# merch-hat.net
KiCad netlist of a schematic drawn in EAGLE
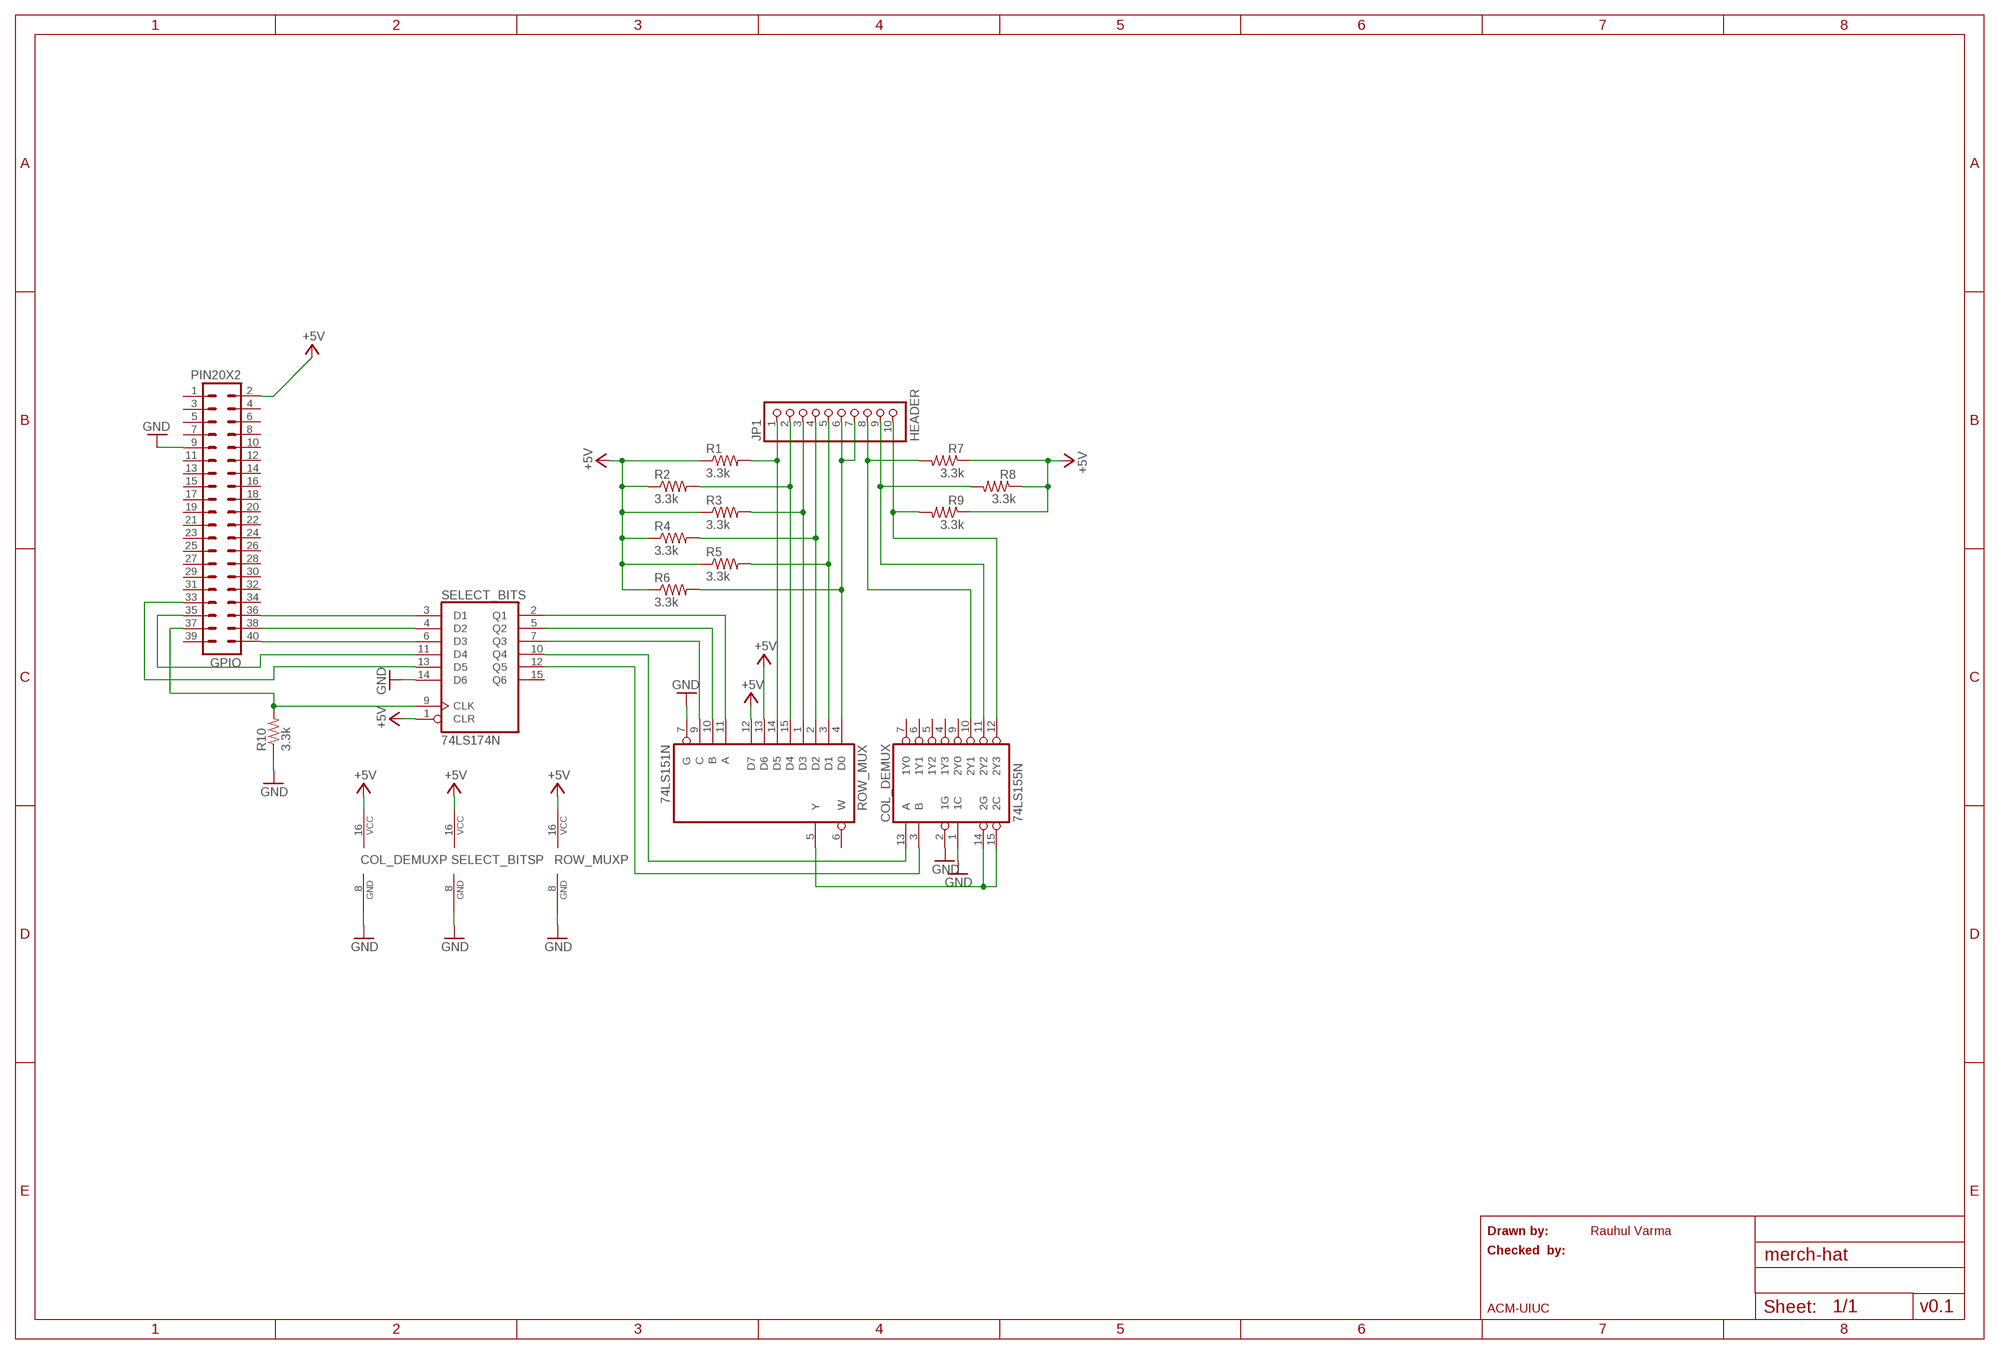
[diagram p0: schematic, sheet 1]

(export (version "E")
  (design (tool "Eeschema 10.0.6"))
  (components
    (comp (ref "COL_DEMUX")
      (value "74LS155N")
      (footprint "eagle-import:DIL16")
      (libsource (lib "eagle-import") (part "74155NLS"))
    )
    (comp (ref "GPIO")
      (value "PIN20X2")
      (footprint "eagle-import:PIN_20X2")
      (libsource (lib "eagle-import") (part "PIN20X2"))
    )
    (comp (ref "JP1")
      (value "HEADER")
      (footprint "eagle-import:1X10")
      (libsource (lib "eagle-import") (part "PINHD-1X10"))
    )
    (comp (ref "R1")
      (value "3.3k")
      (footprint "eagle-import:0207_10")
      (libsource (lib "eagle-import") (part "R-US_0207/10"))
    )
    (comp (ref "R2")
      (value "3.3k")
      (footprint "eagle-import:0207_10")
      (libsource (lib "eagle-import") (part "R-US_0207/10"))
    )
    (comp (ref "R3")
      (value "3.3k")
      (footprint "eagle-import:0207_10")
      (libsource (lib "eagle-import") (part "R-US_0207/10"))
    )
    (comp (ref "R4")
      (value "3.3k")
      (footprint "eagle-import:0207_10")
      (libsource (lib "eagle-import") (part "R-US_0207/10"))
    )
    (comp (ref "R5")
      (value "3.3k")
      (footprint "eagle-import:0207_10")
      (libsource (lib "eagle-import") (part "R-US_0207/10"))
    )
    (comp (ref "R6")
      (value "3.3k")
      (footprint "eagle-import:0207_10")
      (libsource (lib "eagle-import") (part "R-US_0207/10"))
    )
    (comp (ref "R7")
      (value "3.3k")
      (footprint "eagle-import:0207_10")
      (libsource (lib "eagle-import") (part "R-US_0207/10"))
    )
    (comp (ref "R8")
      (value "3.3k")
      (footprint "eagle-import:0207_10")
      (libsource (lib "eagle-import") (part "R-US_0207/10"))
    )
    (comp (ref "R9")
      (value "3.3k")
      (footprint "eagle-import:0207_10")
      (libsource (lib "eagle-import") (part "R-US_0207/10"))
    )
    (comp (ref "R10")
      (value "3.3k")
      (footprint "eagle-import:0207_10")
      (libsource (lib "eagle-import") (part "R-US_0207/10"))
    )
    (comp (ref "ROW_MUX")
      (value "74LS151N")
      (footprint "eagle-import:DIL16")
      (libsource (lib "eagle-import") (part "74151NLS"))
    )
    (comp (ref "SELECT_BITS")
      (value "74LS174N")
      (footprint "eagle-import:DIL16")
      (libsource (lib "eagle-import") (part "74174NLS"))
    )
  )
  (nets
    (net (code "1") (name "+5V") (class "Default")
      (node (ref "COL_DEMUX") (pin "16") (pinfunction "VCC_16") (pintype "power_in"))
      (node (ref "GPIO") (pin "2") (pinfunction "2_2") (pintype "passive"))
      (node (ref "R1") (pin "1") (pinfunction "1_1") (pintype "passive"))
      (node (ref "R2") (pin "1") (pinfunction "1_1") (pintype "passive"))
      (node (ref "R3") (pin "1") (pinfunction "1_1") (pintype "passive"))
      (node (ref "R4") (pin "1") (pinfunction "1_1") (pintype "passive"))
      (node (ref "R5") (pin "1") (pinfunction "1_1") (pintype "passive"))
      (node (ref "R6") (pin "1") (pinfunction "1_1") (pintype "passive"))
      (node (ref "R7") (pin "1") (pinfunction "1_1") (pintype "passive"))
      (node (ref "R8") (pin "1") (pinfunction "1_1") (pintype "passive"))
      (node (ref "R9") (pin "1") (pinfunction "1_1") (pintype "passive"))
      (node (ref "ROW_MUX") (pin "12") (pinfunction "D7_12") (pintype "input"))
      (node (ref "ROW_MUX") (pin "13") (pinfunction "D6_13") (pintype "input"))
      (node (ref "ROW_MUX") (pin "16") (pinfunction "VCC_16") (pintype "power_in"))
      (node (ref "SELECT_BITS") (pin "1") (pinfunction "CLR_1") (pintype "input"))
      (node (ref "SELECT_BITS") (pin "16") (pinfunction "VCC_16") (pintype "power_in"))
    )
    (net (code "2") (name "GND") (class "Default")
      (node (ref "COL_DEMUX") (pin "1") (pinfunction "1C_1") (pintype "input"))
      (node (ref "COL_DEMUX") (pin "2") (pinfunction "1G_2") (pintype "input"))
      (node (ref "COL_DEMUX") (pin "8") (pinfunction "GND_8") (pintype "power_in"))
      (node (ref "GPIO") (pin "9") (pinfunction "9_9") (pintype "passive"))
      (node (ref "R10") (pin "1") (pinfunction "1_1") (pintype "passive"))
      (node (ref "ROW_MUX") (pin "7") (pinfunction "G_7") (pintype "input"))
      (node (ref "ROW_MUX") (pin "8") (pinfunction "GND_8") (pintype "power_in"))
      (node (ref "SELECT_BITS") (pin "14") (pinfunction "D6_14") (pintype "input"))
      (node (ref "SELECT_BITS") (pin "8") (pinfunction "GND_8") (pintype "power_in"))
    )
    (net (code "3") (name "Net-(COL_DEMUXA-2C)") (class "Default")
      (node (ref "COL_DEMUX") (pin "14") (pinfunction "2G_14") (pintype "input"))
      (node (ref "COL_DEMUX") (pin "15") (pinfunction "2C_15") (pintype "input"))
      (node (ref "ROW_MUX") (pin "5") (pinfunction "Y_5") (pintype "output"))
    )
    (net (code "4") (name "Net-(COL_DEMUXA-2Y1)") (class "Default")
      (node (ref "COL_DEMUX") (pin "10") (pinfunction "2Y1_10") (pintype "output"))
      (node (ref "JP1") (pin "8") (pinfunction "8_8") (pintype "passive"))
      (node (ref "R7") (pin "2") (pinfunction "2_2") (pintype "passive"))
    )
    (net (code "5") (name "Net-(COL_DEMUXA-2Y2)") (class "Default")
      (node (ref "COL_DEMUX") (pin "11") (pinfunction "2Y2_11") (pintype "output"))
      (node (ref "JP1") (pin "9") (pinfunction "9_9") (pintype "passive"))
      (node (ref "R8") (pin "2") (pinfunction "2_2") (pintype "passive"))
    )
    (net (code "6") (name "Net-(COL_DEMUXA-2Y3)") (class "Default")
      (node (ref "COL_DEMUX") (pin "12") (pinfunction "2Y3_12") (pintype "output"))
      (node (ref "JP1") (pin "10") (pinfunction "10_10") (pintype "passive"))
      (node (ref "R9") (pin "2") (pinfunction "2_2") (pintype "passive"))
    )
    (net (code "7") (name "Net-(COL_DEMUXA-A)") (class "Default")
      (node (ref "COL_DEMUX") (pin "13") (pinfunction "A_13") (pintype "input"))
      (node (ref "SELECT_BITS") (pin "10") (pinfunction "Q4_10") (pintype "output"))
    )
    (net (code "8") (name "Net-(COL_DEMUXA-B)") (class "Default")
      (node (ref "COL_DEMUX") (pin "3") (pinfunction "B_3") (pintype "input"))
      (node (ref "SELECT_BITS") (pin "12") (pinfunction "Q5_12") (pintype "output"))
    )
    (net (code "9") (name "Net-(ROW_MUXA-A)") (class "Default")
      (node (ref "ROW_MUX") (pin "11") (pinfunction "A_11") (pintype "input"))
      (node (ref "SELECT_BITS") (pin "2") (pinfunction "Q1_2") (pintype "output"))
    )
    (net (code "10") (name "Net-(ROW_MUXA-B)") (class "Default")
      (node (ref "ROW_MUX") (pin "10") (pinfunction "B_10") (pintype "input"))
      (node (ref "SELECT_BITS") (pin "5") (pinfunction "Q2_5") (pintype "output"))
    )
    (net (code "11") (name "Net-(ROW_MUXA-C)") (class "Default")
      (node (ref "ROW_MUX") (pin "9") (pinfunction "C_9") (pintype "input"))
      (node (ref "SELECT_BITS") (pin "7") (pinfunction "Q3_7") (pintype "output"))
    )
    (net (code "12") (name "Net-(ROW_MUXA-D0)") (class "Default")
      (node (ref "JP1") (pin "6") (pinfunction "6_6") (pintype "passive"))
      (node (ref "JP1") (pin "7") (pinfunction "7_7") (pintype "passive"))
      (node (ref "R6") (pin "2") (pinfunction "2_2") (pintype "passive"))
      (node (ref "ROW_MUX") (pin "4") (pinfunction "D0_4") (pintype "input"))
    )
    (net (code "13") (name "Net-(ROW_MUXA-D1)") (class "Default")
      (node (ref "JP1") (pin "5") (pinfunction "5_5") (pintype "passive"))
      (node (ref "R5") (pin "2") (pinfunction "2_2") (pintype "passive"))
      (node (ref "ROW_MUX") (pin "3") (pinfunction "D1_3") (pintype "input"))
    )
    (net (code "14") (name "Net-(ROW_MUXA-D2)") (class "Default")
      (node (ref "JP1") (pin "4") (pinfunction "4_4") (pintype "passive"))
      (node (ref "R4") (pin "2") (pinfunction "2_2") (pintype "passive"))
      (node (ref "ROW_MUX") (pin "2") (pinfunction "D2_2") (pintype "input"))
    )
    (net (code "15") (name "Net-(ROW_MUXA-D3)") (class "Default")
      (node (ref "JP1") (pin "3") (pinfunction "3_3") (pintype "passive"))
      (node (ref "R3") (pin "2") (pinfunction "2_2") (pintype "passive"))
      (node (ref "ROW_MUX") (pin "1") (pinfunction "D3_1") (pintype "input"))
    )
    (net (code "16") (name "Net-(ROW_MUXA-D4)") (class "Default")
      (node (ref "JP1") (pin "2") (pinfunction "2_2") (pintype "passive"))
      (node (ref "R2") (pin "2") (pinfunction "2_2") (pintype "passive"))
      (node (ref "ROW_MUX") (pin "15") (pinfunction "D4_15") (pintype "input"))
    )
    (net (code "17") (name "Net-(ROW_MUXA-D5)") (class "Default")
      (node (ref "JP1") (pin "1") (pinfunction "1_1") (pintype "passive"))
      (node (ref "R1") (pin "2") (pinfunction "2_2") (pintype "passive"))
      (node (ref "ROW_MUX") (pin "14") (pinfunction "D5_14") (pintype "input"))
    )
    (net (code "18") (name "Net-(SELECT_BITSA-CLK)") (class "Default")
      (node (ref "GPIO") (pin "37") (pinfunction "37_37") (pintype "passive"))
      (node (ref "R10") (pin "2") (pinfunction "2_2") (pintype "passive"))
      (node (ref "SELECT_BITS") (pin "9") (pinfunction "CLK_9") (pintype "input"))
    )
    (net (code "19") (name "Net-(SELECT_BITSA-D1)") (class "Default")
      (node (ref "GPIO") (pin "36") (pinfunction "36_36") (pintype "passive"))
      (node (ref "SELECT_BITS") (pin "3") (pinfunction "D1_3") (pintype "input"))
    )
    (net (code "20") (name "Net-(SELECT_BITSA-D2)") (class "Default")
      (node (ref "GPIO") (pin "38") (pinfunction "38_38") (pintype "passive"))
      (node (ref "SELECT_BITS") (pin "4") (pinfunction "D2_4") (pintype "input"))
    )
    (net (code "21") (name "Net-(SELECT_BITSA-D3)") (class "Default")
      (node (ref "GPIO") (pin "40") (pinfunction "40_40") (pintype "passive"))
      (node (ref "SELECT_BITS") (pin "6") (pinfunction "D3_6") (pintype "input"))
    )
    (net (code "22") (name "Net-(SELECT_BITSA-D4)") (class "Default")
      (node (ref "GPIO") (pin "35") (pinfunction "35_35") (pintype "passive"))
      (node (ref "SELECT_BITS") (pin "11") (pinfunction "D4_11") (pintype "input"))
    )
    (net (code "23") (name "Net-(SELECT_BITSA-D5)") (class "Default")
      (node (ref "GPIO") (pin "33") (pinfunction "33_33") (pintype "passive"))
      (node (ref "SELECT_BITS") (pin "13") (pinfunction "D5_13") (pintype "input"))
    )
    (net (code "24") (name "unconnected-(COL_DEMUXA-1Y0-Pad7)") (class "Default")
      (node (ref "COL_DEMUX") (pin "7") (pinfunction "1Y0_7") (pintype "output"))
    )
    (net (code "25") (name "unconnected-(COL_DEMUXA-1Y1-Pad6)") (class "Default")
      (node (ref "COL_DEMUX") (pin "6") (pinfunction "1Y1_6") (pintype "output"))
    )
    (net (code "26") (name "unconnected-(COL_DEMUXA-1Y2-Pad5)") (class "Default")
      (node (ref "COL_DEMUX") (pin "5") (pinfunction "1Y2_5") (pintype "output"))
    )
    (net (code "27") (name "unconnected-(COL_DEMUXA-1Y3-Pad4)") (class "Default")
      (node (ref "COL_DEMUX") (pin "4") (pinfunction "1Y3_4") (pintype "output"))
    )
    (net (code "28") (name "unconnected-(COL_DEMUXA-2Y0-Pad9)") (class "Default")
      (node (ref "COL_DEMUX") (pin "9") (pinfunction "2Y0_9") (pintype "output"))
    )
    (net (code "29") (name "unconnected-(GPIO-Pad1)") (class "Default")
      (node (ref "GPIO") (pin "1") (pinfunction "1_1") (pintype "passive"))
    )
    (net (code "30") (name "unconnected-(GPIO-Pad3)") (class "Default")
      (node (ref "GPIO") (pin "3") (pinfunction "3_3") (pintype "passive"))
    )
    (net (code "31") (name "unconnected-(GPIO-Pad4)") (class "Default")
      (node (ref "GPIO") (pin "4") (pinfunction "4_4") (pintype "passive"))
    )
    (net (code "32") (name "unconnected-(GPIO-Pad5)") (class "Default")
      (node (ref "GPIO") (pin "5") (pinfunction "5_5") (pintype "passive"))
    )
    (net (code "33") (name "unconnected-(GPIO-Pad6)") (class "Default")
      (node (ref "GPIO") (pin "6") (pinfunction "6_6") (pintype "passive"))
    )
    (net (code "34") (name "unconnected-(GPIO-Pad7)") (class "Default")
      (node (ref "GPIO") (pin "7") (pinfunction "7_7") (pintype "passive"))
    )
    (net (code "35") (name "unconnected-(GPIO-Pad8)") (class "Default")
      (node (ref "GPIO") (pin "8") (pinfunction "8_8") (pintype "passive"))
    )
    (net (code "36") (name "unconnected-(GPIO-Pad10)") (class "Default")
      (node (ref "GPIO") (pin "10") (pinfunction "10_10") (pintype "passive"))
    )
    (net (code "37") (name "unconnected-(GPIO-Pad11)") (class "Default")
      (node (ref "GPIO") (pin "11") (pinfunction "11_11") (pintype "passive"))
    )
    (net (code "38") (name "unconnected-(GPIO-Pad12)") (class "Default")
      (node (ref "GPIO") (pin "12") (pinfunction "12_12") (pintype "passive"))
    )
    (net (code "39") (name "unconnected-(GPIO-Pad13)") (class "Default")
      (node (ref "GPIO") (pin "13") (pinfunction "13_13") (pintype "passive"))
    )
    (net (code "40") (name "unconnected-(GPIO-Pad14)") (class "Default")
      (node (ref "GPIO") (pin "14") (pinfunction "14_14") (pintype "passive"))
    )
    (net (code "41") (name "unconnected-(GPIO-Pad15)") (class "Default")
      (node (ref "GPIO") (pin "15") (pinfunction "15_15") (pintype "passive"))
    )
    (net (code "42") (name "unconnected-(GPIO-Pad16)") (class "Default")
      (node (ref "GPIO") (pin "16") (pinfunction "16_16") (pintype "passive"))
    )
    (net (code "43") (name "unconnected-(GPIO-Pad17)") (class "Default")
      (node (ref "GPIO") (pin "17") (pinfunction "17_17") (pintype "passive"))
    )
    (net (code "44") (name "unconnected-(GPIO-Pad18)") (class "Default")
      (node (ref "GPIO") (pin "18") (pinfunction "18_18") (pintype "passive"))
    )
    (net (code "45") (name "unconnected-(GPIO-Pad19)") (class "Default")
      (node (ref "GPIO") (pin "19") (pinfunction "19_19") (pintype "passive"))
    )
    (net (code "46") (name "unconnected-(GPIO-Pad20)") (class "Default")
      (node (ref "GPIO") (pin "20") (pinfunction "20_20") (pintype "passive"))
    )
    (net (code "47") (name "unconnected-(GPIO-Pad21)") (class "Default")
      (node (ref "GPIO") (pin "21") (pinfunction "21_21") (pintype "passive"))
    )
    (net (code "48") (name "unconnected-(GPIO-Pad22)") (class "Default")
      (node (ref "GPIO") (pin "22") (pinfunction "22_22") (pintype "passive"))
    )
    (net (code "49") (name "unconnected-(GPIO-Pad23)") (class "Default")
      (node (ref "GPIO") (pin "23") (pinfunction "23_23") (pintype "passive"))
    )
    (net (code "50") (name "unconnected-(GPIO-Pad24)") (class "Default")
      (node (ref "GPIO") (pin "24") (pinfunction "24_24") (pintype "passive"))
    )
    (net (code "51") (name "unconnected-(GPIO-Pad25)") (class "Default")
      (node (ref "GPIO") (pin "25") (pinfunction "25_25") (pintype "passive"))
    )
    (net (code "52") (name "unconnected-(GPIO-Pad26)") (class "Default")
      (node (ref "GPIO") (pin "26") (pinfunction "26_26") (pintype "passive"))
    )
    (net (code "53") (name "unconnected-(GPIO-Pad27)") (class "Default")
      (node (ref "GPIO") (pin "27") (pinfunction "27_27") (pintype "passive"))
    )
    (net (code "54") (name "unconnected-(GPIO-Pad28)") (class "Default")
      (node (ref "GPIO") (pin "28") (pinfunction "28_28") (pintype "passive"))
    )
    (net (code "55") (name "unconnected-(GPIO-Pad29)") (class "Default")
      (node (ref "GPIO") (pin "29") (pinfunction "29_29") (pintype "passive"))
    )
    (net (code "56") (name "unconnected-(GPIO-Pad30)") (class "Default")
      (node (ref "GPIO") (pin "30") (pinfunction "30_30") (pintype "passive"))
    )
    (net (code "57") (name "unconnected-(GPIO-Pad31)") (class "Default")
      (node (ref "GPIO") (pin "31") (pinfunction "31_31") (pintype "passive"))
    )
    (net (code "58") (name "unconnected-(GPIO-Pad32)") (class "Default")
      (node (ref "GPIO") (pin "32") (pinfunction "32_32") (pintype "passive"))
    )
    (net (code "59") (name "unconnected-(GPIO-Pad34)") (class "Default")
      (node (ref "GPIO") (pin "34") (pinfunction "34_34") (pintype "passive"))
    )
    (net (code "60") (name "unconnected-(GPIO-Pad39)") (class "Default")
      (node (ref "GPIO") (pin "39") (pinfunction "39_39") (pintype "passive"))
    )
    (net (code "61") (name "unconnected-(ROW_MUXA-W-Pad6)") (class "Default")
      (node (ref "ROW_MUX") (pin "6") (pinfunction "W_6") (pintype "output"))
    )
    (net (code "62") (name "unconnected-(SELECT_BITSA-Q6-Pad15)") (class "Default")
      (node (ref "SELECT_BITS") (pin "15") (pinfunction "Q6_15") (pintype "output"))
    )
  )
)
